# TPS54627DDAR.net
KiCad netlist of a schematic drawn in Altium Designer
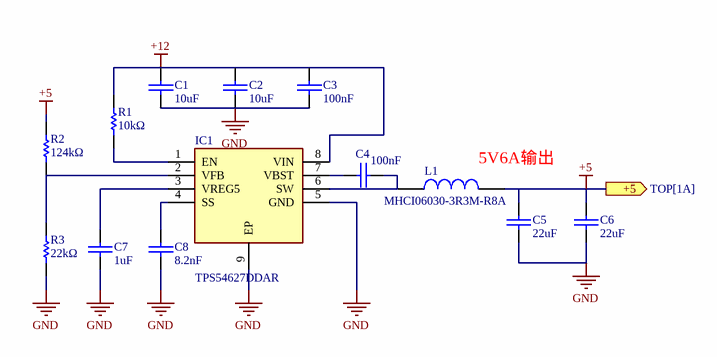
[diagram p0: TPS54627DDAR.SchDoc]

(export (version "E")
  (design (tool "Eeschema 10.0.6"))
  (components
    (comp (ref "C1")
      (value "10uF")
      (footprint "C_1206")
      (description "贴片电容")
      (libsource (lib "IntLib-Passive") (part "Cap_Chip"))
    )
    (comp (ref "C2")
      (value "10uF")
      (footprint "C_1206")
      (description "贴片电容")
      (libsource (lib "IntLib-Passive") (part "Cap_Chip"))
    )
    (comp (ref "C3")
      (value "100nF")
      (footprint "C_0603")
      (description "贴片电容")
      (libsource (lib "IntLib-Passive") (part "Cap_Chip"))
    )
    (comp (ref "C4")
      (value "100nF")
      (footprint "C_0603")
      (description "贴片电容")
      (libsource (lib "IntLib-Passive") (part "Cap_Chip"))
    )
    (comp (ref "C5")
      (value "22uF")
      (footprint "C_0805")
      (description "贴片电容")
      (libsource (lib "IntLib-Passive") (part "Cap_Chip"))
    )
    (comp (ref "C6")
      (value "22uF")
      (footprint "C_0805")
      (description "贴片电容")
      (libsource (lib "IntLib-Passive") (part "Cap_Chip"))
    )
    (comp (ref "C7")
      (value "1uF")
      (footprint "C_0603")
      (description "贴片电容")
      (libsource (lib "IntLib-Passive") (part "Cap_Chip"))
    )
    (comp (ref "C8")
      (value "8.2nF")
      (footprint "C_0402")
      (description "贴片电容")
      (libsource (lib "IntLib-Passive") (part "Cap_Chip"))
    )
    (comp (ref "IC1")
      (value "TPS54627DDAR")
      (footprint "IntLib-IC:SOIC-8-PowerPAD")
      (description "DC-DC 降压芯片")
      (libsource (lib "IC-TI") (part "TPS54627DDAR"))
    )
    (comp (ref "L1")
      (value "MHCI06030-3R3M-R8A")
      (footprint "Ind-SMD_7.3x6.6")
      (description "一体成型功率电感")
      (libsource (lib "IntLib-Passive") (part "Ind_Molded"))
    )
    (comp (ref "R1")
      (value "10kΩ")
      (footprint "R_0402")
      (description "贴片电阻")
      (libsource (lib "IntLib-Passive") (part "Res_Chip"))
    )
    (comp (ref "R2")
      (value "124kΩ")
      (footprint "R_0402")
      (description "贴片电阻")
      (libsource (lib "IntLib-Passive") (part "Res_Chip"))
    )
    (comp (ref "R3")
      (value "22kΩ")
      (footprint "R_0402")
      (description "贴片电阻")
      (libsource (lib "IntLib-Passive") (part "Res_Chip"))
    )
  )
  (nets
    (net (code "1") (name "+5") (class "Default")
      (node (ref "C5") (pin "2") (pinfunction "2_2") (pintype "passive"))
      (node (ref "C6") (pin "2") (pinfunction "2_2") (pintype "passive"))
      (node (ref "L1") (pin "2") (pinfunction "2_2") (pintype "passive"))
      (node (ref "R2") (pin "1") (pinfunction "1_1") (pintype "passive"))
    )
    (net (code "2") (name "+12") (class "Default")
      (node (ref "C1") (pin "2") (pinfunction "2_2") (pintype "passive"))
      (node (ref "C2") (pin "2") (pinfunction "2_2") (pintype "passive"))
      (node (ref "C3") (pin "2") (pinfunction "2_2") (pintype "passive"))
      (node (ref "IC1") (pin "8") (pinfunction "VIN_8") (pintype "passive"))
      (node (ref "R1") (pin "2") (pinfunction "2_2") (pintype "passive"))
    )
    (net (code "3") (name "GND") (class "Default")
      (node (ref "C1") (pin "1") (pinfunction "1_1") (pintype "passive"))
      (node (ref "C2") (pin "1") (pinfunction "1_1") (pintype "passive"))
      (node (ref "C3") (pin "1") (pinfunction "1_1") (pintype "passive"))
      (node (ref "C5") (pin "1") (pinfunction "1_1") (pintype "passive"))
      (node (ref "C6") (pin "1") (pinfunction "1_1") (pintype "passive"))
      (node (ref "C7") (pin "2") (pinfunction "2_2") (pintype "passive"))
      (node (ref "C8") (pin "1") (pinfunction "1_1") (pintype "passive"))
      (node (ref "IC1") (pin "5") (pinfunction "GND_5") (pintype "passive"))
      (node (ref "IC1") (pin "9") (pinfunction "EP_9") (pintype "passive"))
      (node (ref "R3") (pin "1") (pinfunction "1_1") (pintype "passive"))
    )
    (net (code "4") (name "Net-(IC1-EN)") (class "Default")
      (node (ref "IC1") (pin "1") (pinfunction "EN_1") (pintype "passive"))
      (node (ref "R1") (pin "1") (pinfunction "1_1") (pintype "passive"))
    )
    (net (code "5") (name "Net-(IC1-SS)") (class "Default")
      (node (ref "C8") (pin "2") (pinfunction "2_2") (pintype "passive"))
      (node (ref "IC1") (pin "4") (pinfunction "SS_4") (pintype "passive"))
    )
    (net (code "6") (name "Net-(IC1-SW)") (class "Default")
      (node (ref "C4") (pin "1") (pinfunction "1_1") (pintype "passive"))
      (node (ref "IC1") (pin "6") (pinfunction "SW_6") (pintype "passive"))
      (node (ref "L1") (pin "1") (pinfunction "1_1") (pintype "passive"))
    )
    (net (code "7") (name "Net-(IC1-VBST)") (class "Default")
      (node (ref "C4") (pin "2") (pinfunction "2_2") (pintype "passive"))
      (node (ref "IC1") (pin "7") (pinfunction "VBST_7") (pintype "passive"))
    )
    (net (code "8") (name "Net-(IC1-VFB)") (class "Default")
      (node (ref "IC1") (pin "2") (pinfunction "VFB_2") (pintype "passive"))
      (node (ref "R2") (pin "2") (pinfunction "2_2") (pintype "passive"))
      (node (ref "R3") (pin "2") (pinfunction "2_2") (pintype "passive"))
    )
    (net (code "9") (name "Net-(IC1-VREG5)") (class "Default")
      (node (ref "C7") (pin "1") (pinfunction "1_1") (pintype "passive"))
      (node (ref "IC1") (pin "3") (pinfunction "VREG5_3") (pintype "passive"))
    )
  )
)
